# IMU_final.net
KiCad netlist of a schematic drawn in EAGLE
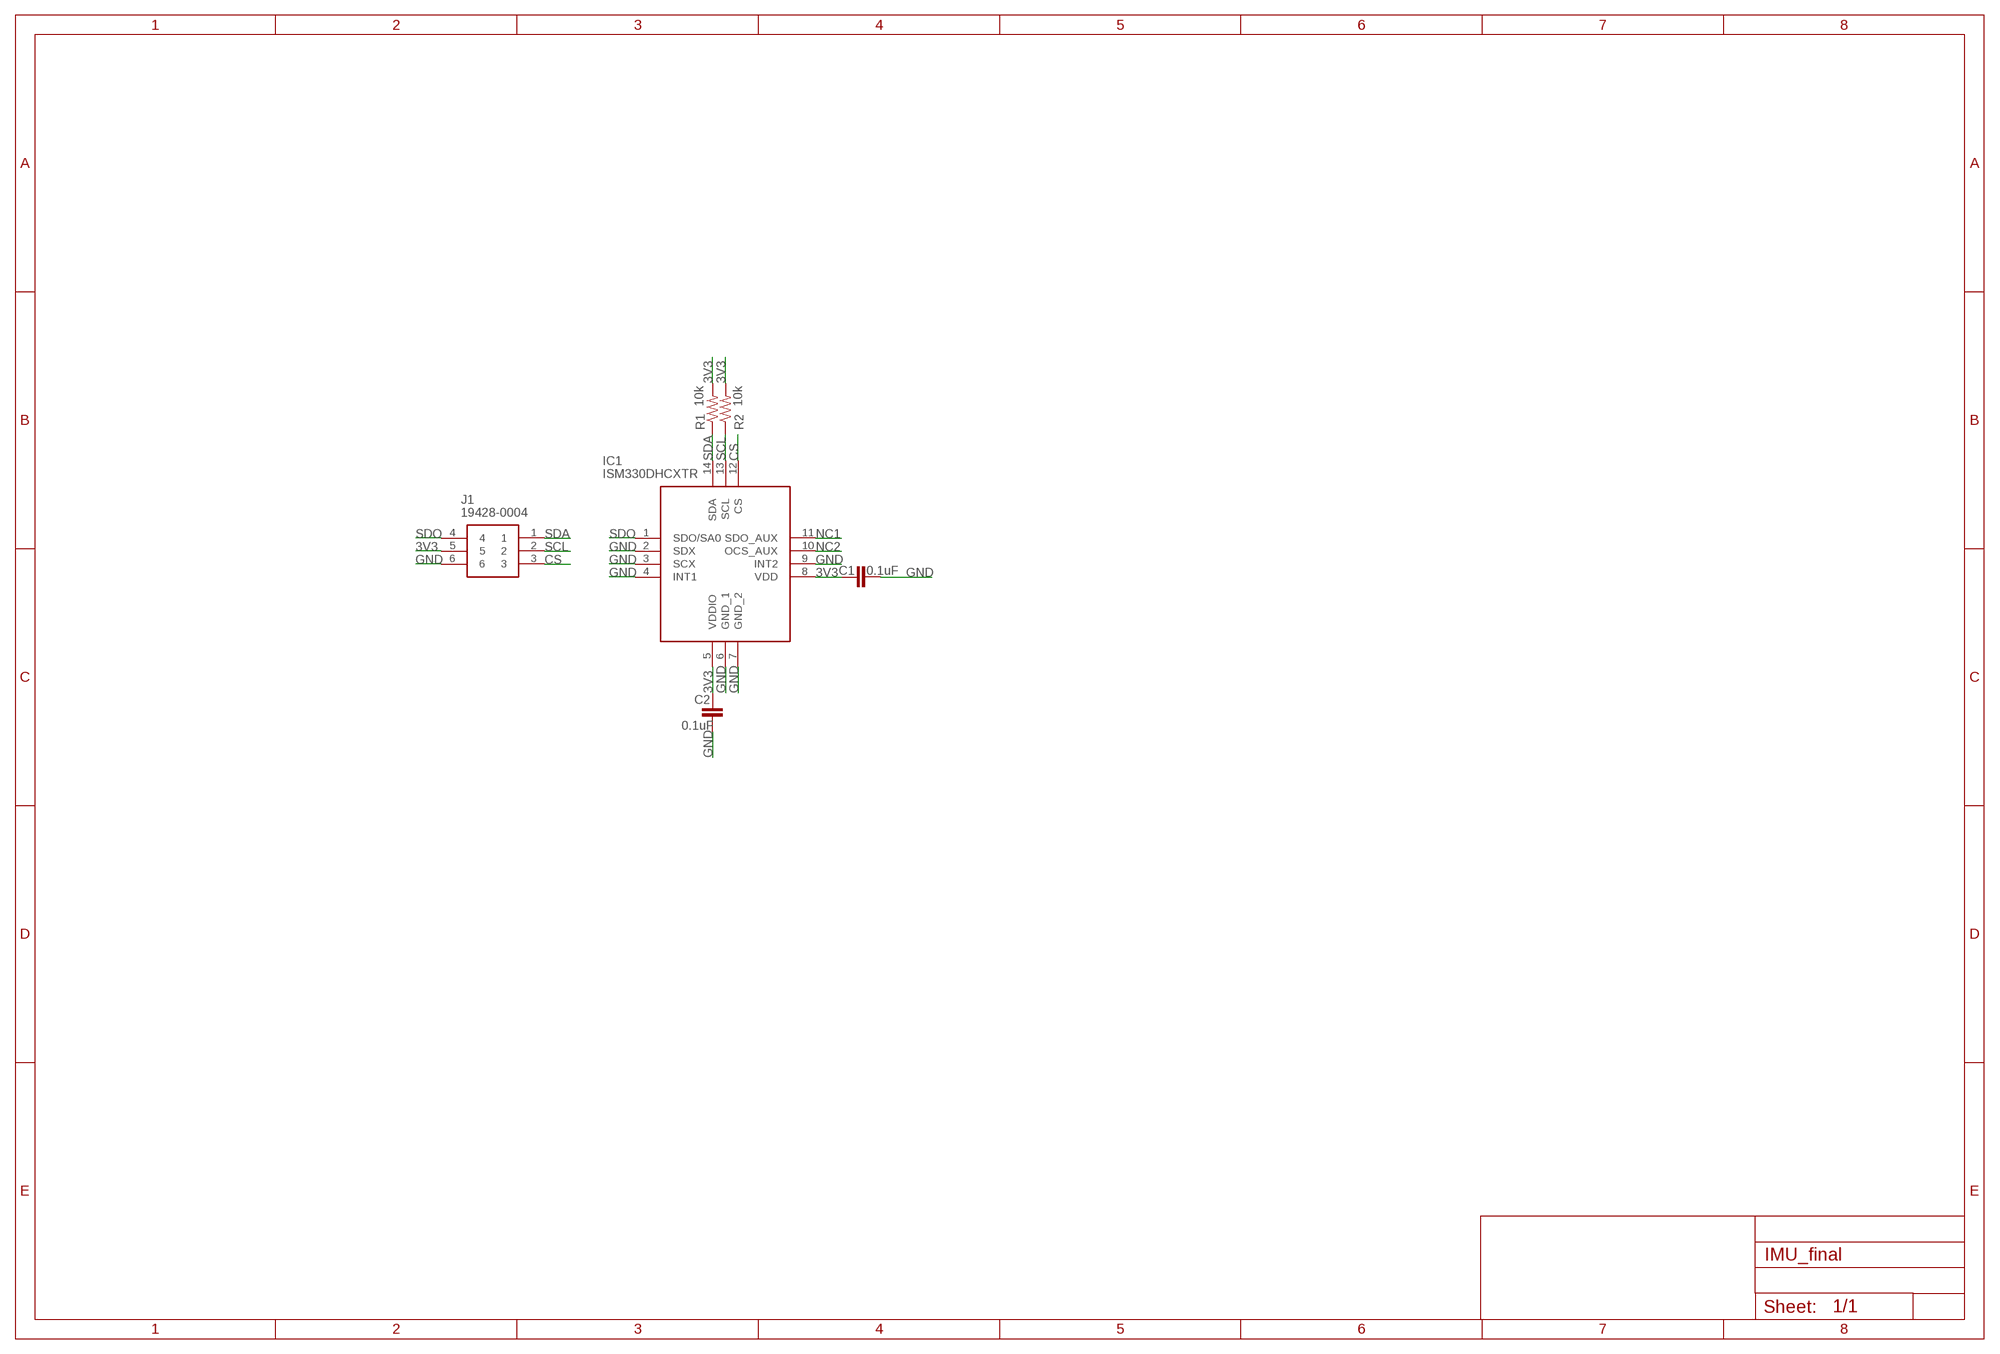
[diagram p0: schematic, sheet 1]

(export (version "E")
  (design (tool "Eeschema 10.0.6"))
  (components
    (comp (ref "C1")
      (value "0.1uF")
      (footprint "eagle-import:0603")
      (libsource (lib "eagle-import") (part "0.1UF-0603-25V-(+80/-20%)"))
    )
    (comp (ref "C2")
      (value "0.1uF")
      (footprint "eagle-import:0603")
      (libsource (lib "eagle-import") (part "0.1UF-0603-25V-(+80/-20%)"))
    )
    (comp (ref "IC1")
      (value "ISM330DHCXTR")
      (footprint "eagle-import:LGA-14(2.5X3X0.86)")
      (fields (field (name "MOUSER_PART_NUMBER") "511-ISM330DHCXTR"))
      (libsource (lib "eagle-import") (part "ISM330DHCXTR"))
    )
    (comp (ref "J1")
      (value "19428-0004")
      (footprint "eagle-import:194280004")
      (fields (field (name "MOUSER_PART_NUMBER") "538-19428-0004"))
      (libsource (lib "eagle-import") (part "19428-0004"))
    )
    (comp (ref "R1")
      (value "10k")
      (footprint "eagle-import:0603")
      (libsource (lib "eagle-import") (part "10KOHM-0603-1/10W-1%"))
    )
    (comp (ref "R2")
      (value "10k")
      (footprint "eagle-import:0603")
      (libsource (lib "eagle-import") (part "10KOHM-0603-1/10W-1%"))
    )
  )
  (nets
    (net (code "1") (name "/3V3") (class "Default")
      (node (ref "C1") (pin "1") (pinfunction "1_1") (pintype "passive"))
      (node (ref "C2") (pin "1") (pinfunction "1_1") (pintype "passive"))
      (node (ref "IC1") (pin "5") (pinfunction "VDDIO_5") (pintype "bidirectional"))
      (node (ref "IC1") (pin "8") (pinfunction "VDD_8") (pintype "bidirectional"))
      (node (ref "J1") (pin "5") (pinfunction "5_5") (pintype "bidirectional"))
      (node (ref "R1") (pin "2") (pinfunction "2_2") (pintype "passive"))
      (node (ref "R2") (pin "2") (pinfunction "2_2") (pintype "passive"))
    )
    (net (code "2") (name "/CS") (class "Default")
      (node (ref "IC1") (pin "12") (pinfunction "CS_12") (pintype "bidirectional"))
      (node (ref "J1") (pin "3") (pinfunction "3_3") (pintype "bidirectional"))
    )
    (net (code "3") (name "/GND") (class "Default")
      (node (ref "C1") (pin "2") (pinfunction "2_2") (pintype "passive"))
      (node (ref "C2") (pin "2") (pinfunction "2_2") (pintype "passive"))
      (node (ref "IC1") (pin "2") (pinfunction "SDX_2") (pintype "bidirectional"))
      (node (ref "IC1") (pin "3") (pinfunction "SCX_3") (pintype "bidirectional"))
      (node (ref "IC1") (pin "4") (pinfunction "INT1_4") (pintype "bidirectional"))
      (node (ref "IC1") (pin "6") (pinfunction "GND_1_6") (pintype "bidirectional"))
      (node (ref "IC1") (pin "7") (pinfunction "GND_2_7") (pintype "bidirectional"))
      (node (ref "IC1") (pin "9") (pinfunction "INT2_9") (pintype "bidirectional"))
      (node (ref "J1") (pin "6") (pinfunction "6_6") (pintype "bidirectional"))
    )
    (net (code "4") (name "/NC1") (class "Default")
      (node (ref "IC1") (pin "11") (pinfunction "SDO_AUX_11") (pintype "bidirectional"))
    )
    (net (code "5") (name "/NC2") (class "Default")
      (node (ref "IC1") (pin "10") (pinfunction "OCS_AUX_10") (pintype "bidirectional"))
    )
    (net (code "6") (name "/SCL") (class "Default")
      (node (ref "IC1") (pin "13") (pinfunction "SCL_13") (pintype "bidirectional"))
      (node (ref "J1") (pin "2") (pinfunction "2_2") (pintype "bidirectional"))
      (node (ref "R2") (pin "1") (pinfunction "1_1") (pintype "passive"))
    )
    (net (code "7") (name "/SDA") (class "Default")
      (node (ref "IC1") (pin "14") (pinfunction "SDA_14") (pintype "bidirectional"))
      (node (ref "J1") (pin "1") (pinfunction "1_1") (pintype "bidirectional"))
      (node (ref "R1") (pin "1") (pinfunction "1_1") (pintype "passive"))
    )
    (net (code "8") (name "/SDO") (class "Default")
      (node (ref "IC1") (pin "1") (pinfunction "SDO/SA0_1") (pintype "bidirectional"))
      (node (ref "J1") (pin "4") (pinfunction "4_4") (pintype "bidirectional"))
    )
  )
)
